# SHDN-CURRENT-S09-V00-PSU-5V.net
KiCad netlist of a schematic drawn in Altium Designer
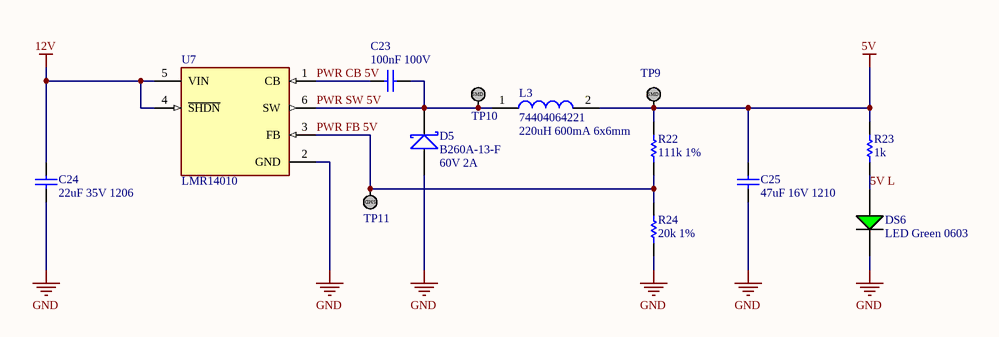
[diagram p0: SHDN-CURRENT-S09-V00-PSU-5V.SchDoc]

(export (version "E")
  (design (tool "Eeschema 10.0.6"))
  (components
    (comp (ref "C23")
      (value "100nF 100V")
      (footprint "Cap_Ceramic_0603")
      (description "Capacitor, Ceramic, SMD, 100nF, 100V, 5%, X7R, 0603")
      (libsource (lib "StandardCapacitors") (part "100nF 100V 5% X7R 0603"))
    )
    (comp (ref "C24")
      (value "22uF 35V 1206")
      (footprint "Cap_Ceramic_1206")
      (description "Capacitor, Ceramic, SMD, 22uF, 35V, 10%, X7R, 1206")
      (libsource (lib "StandardCapacitors") (part "22uF 35V 10% X7R 1206"))
    )
    (comp (ref "C25")
      (value "47uF 16V 1210")
      (footprint "Cap_Ceramic_1210")
      (description "Capacitor, Ceramic, SMD, 47uF, 16V, 5%, X7R, 1210")
      (libsource (lib "StandardCapacitors") (part "47uF 16V 10% X7R 1210"))
    )
    (comp (ref "D5")
      (value "B260A-13-F")
      (footprint "SMA")
      (description "Diode, Schottky Barrier Rectifier, 60 V, 2 A, B260A-13-F")
      (libsource (lib "QUTMS_DiodeLibrary") (part "B260A-13-F"))
    )
    (comp (ref "DS6")
      (value "LED Green 0603")
      (footprint "LED GREEN 0603")
      (libsource (lib "QUTMS_LEDLibrary") (part "LED Green 0603"))
    )
    (comp (ref "L3")
      (value "74404064221")
      (footprint "Inductor_6x6mm")
      (description "FIXED IND 220UH 660MA 850 MOHM")
      (libsource (lib "QUTMS_InductorLibrary") (part "74404064221"))
    )
    (comp (ref "R22")
      (value "111k 1%")
      (footprint "Res_ThinFilm_0603")
      (description "Resistor, SMD, 111k, 0.1W, 1%, 0603")
      (libsource (lib "StandardResistors") (part "111k 1% 0603"))
    )
    (comp (ref "R23")
      (value "1k")
      (footprint "Res_ThinFilm_0603")
      (description "Resistor, SMD, 1k, 0.1W, 5%, 0603")
      (libsource (lib "StandardResistors") (part "1k 5% 0603"))
    )
    (comp (ref "R24")
      (value "20k 1%")
      (footprint "Res_ThinFilm_0603")
      (description "Resistor, SMD, 20k, 0.1W, 1%, 0603")
      (libsource (lib "StandardResistors") (part "20k 1% 0603"))
    )
    (comp (ref "TP9")
      (value "TestPoint_SMD")
      (footprint "TestPointSMD")
      (libsource (lib "StandardTest") (part "TestPoint_SMD"))
    )
    (comp (ref "TP10")
      (value "TestPoint_SMD")
      (footprint "TestPointSMD")
      (libsource (lib "StandardTest") (part "TestPoint_SMD"))
    )
    (comp (ref "TP11")
      (value "TestPoint_SMD")
      (footprint "TestPointSMD")
      (libsource (lib "StandardTest") (part "TestPoint_SMD"))
    )
    (comp (ref "U7")
      (value "LMR14010")
      (footprint "LMR14010")
      (libsource (lib "QUTMS_PowerSupplyLibrary") (part "LMR14010"))
    )
  )
  (nets
    (net (code "1") (name "/5V L") (class "Default")
      (node (ref "DS6") (pin "1") (pinfunction "A_1") (pintype "passive"))
      (node (ref "R23") (pin "1") (pinfunction "1_1") (pintype "passive"))
    )
    (net (code "2") (name "/PWR CB 5V") (class "Default")
      (node (ref "C23") (pin "1") (pinfunction "1_1") (pintype "passive"))
      (node (ref "U7") (pin "1") (pinfunction "CB_1") (pintype "input"))
    )
    (net (code "3") (name "/PWR FB 5V") (class "Default")
      (node (ref "R22") (pin "1") (pinfunction "1_1") (pintype "passive"))
      (node (ref "R24") (pin "2") (pinfunction "2_2") (pintype "passive"))
      (node (ref "TP11") (pin "1") (pinfunction "1_1") (pintype "passive"))
      (node (ref "U7") (pin "3") (pinfunction "FB_3") (pintype "input"))
    )
    (net (code "4") (name "/PWR SW 5V") (class "Default")
      (node (ref "C23") (pin "2") (pinfunction "2_2") (pintype "passive"))
      (node (ref "D5") (pin "K") (pinfunction "K_K") (pintype "passive"))
      (node (ref "L3") (pin "1") (pinfunction "1_1") (pintype "passive"))
      (node (ref "TP10") (pin "1") (pinfunction "1_1") (pintype "passive"))
      (node (ref "U7") (pin "6") (pinfunction "SW_6") (pintype "output"))
    )
    (net (code "5") (name "5V") (class "Default")
      (node (ref "C25") (pin "2") (pinfunction "2_2") (pintype "passive"))
      (node (ref "L3") (pin "2") (pinfunction "2_2") (pintype "passive"))
      (node (ref "R22") (pin "2") (pinfunction "2_2") (pintype "passive"))
      (node (ref "R23") (pin "2") (pinfunction "2_2") (pintype "passive"))
      (node (ref "TP9") (pin "1") (pinfunction "1_1") (pintype "passive"))
    )
    (net (code "6") (name "12V") (class "Default")
      (node (ref "C24") (pin "2") (pinfunction "2_2") (pintype "passive"))
      (node (ref "U7") (pin "4") (pinfunction "~{SHDN}_4") (pintype "input"))
      (node (ref "U7") (pin "5") (pinfunction "VIN_5") (pintype "power_in"))
    )
    (net (code "7") (name "GND") (class "Default")
      (node (ref "C24") (pin "1") (pinfunction "1_1") (pintype "passive"))
      (node (ref "C25") (pin "1") (pinfunction "1_1") (pintype "passive"))
      (node (ref "D5") (pin "A") (pinfunction "A_A") (pintype "passive"))
      (node (ref "DS6") (pin "2") (pinfunction "C_2") (pintype "passive"))
      (node (ref "R24") (pin "1") (pinfunction "1_1") (pintype "passive"))
      (node (ref "U7") (pin "2") (pinfunction "GND_2") (pintype "power_in"))
    )
  )
)
